# originalSWEEP.net
KiCad netlist of a schematic drawn in Altium Designer
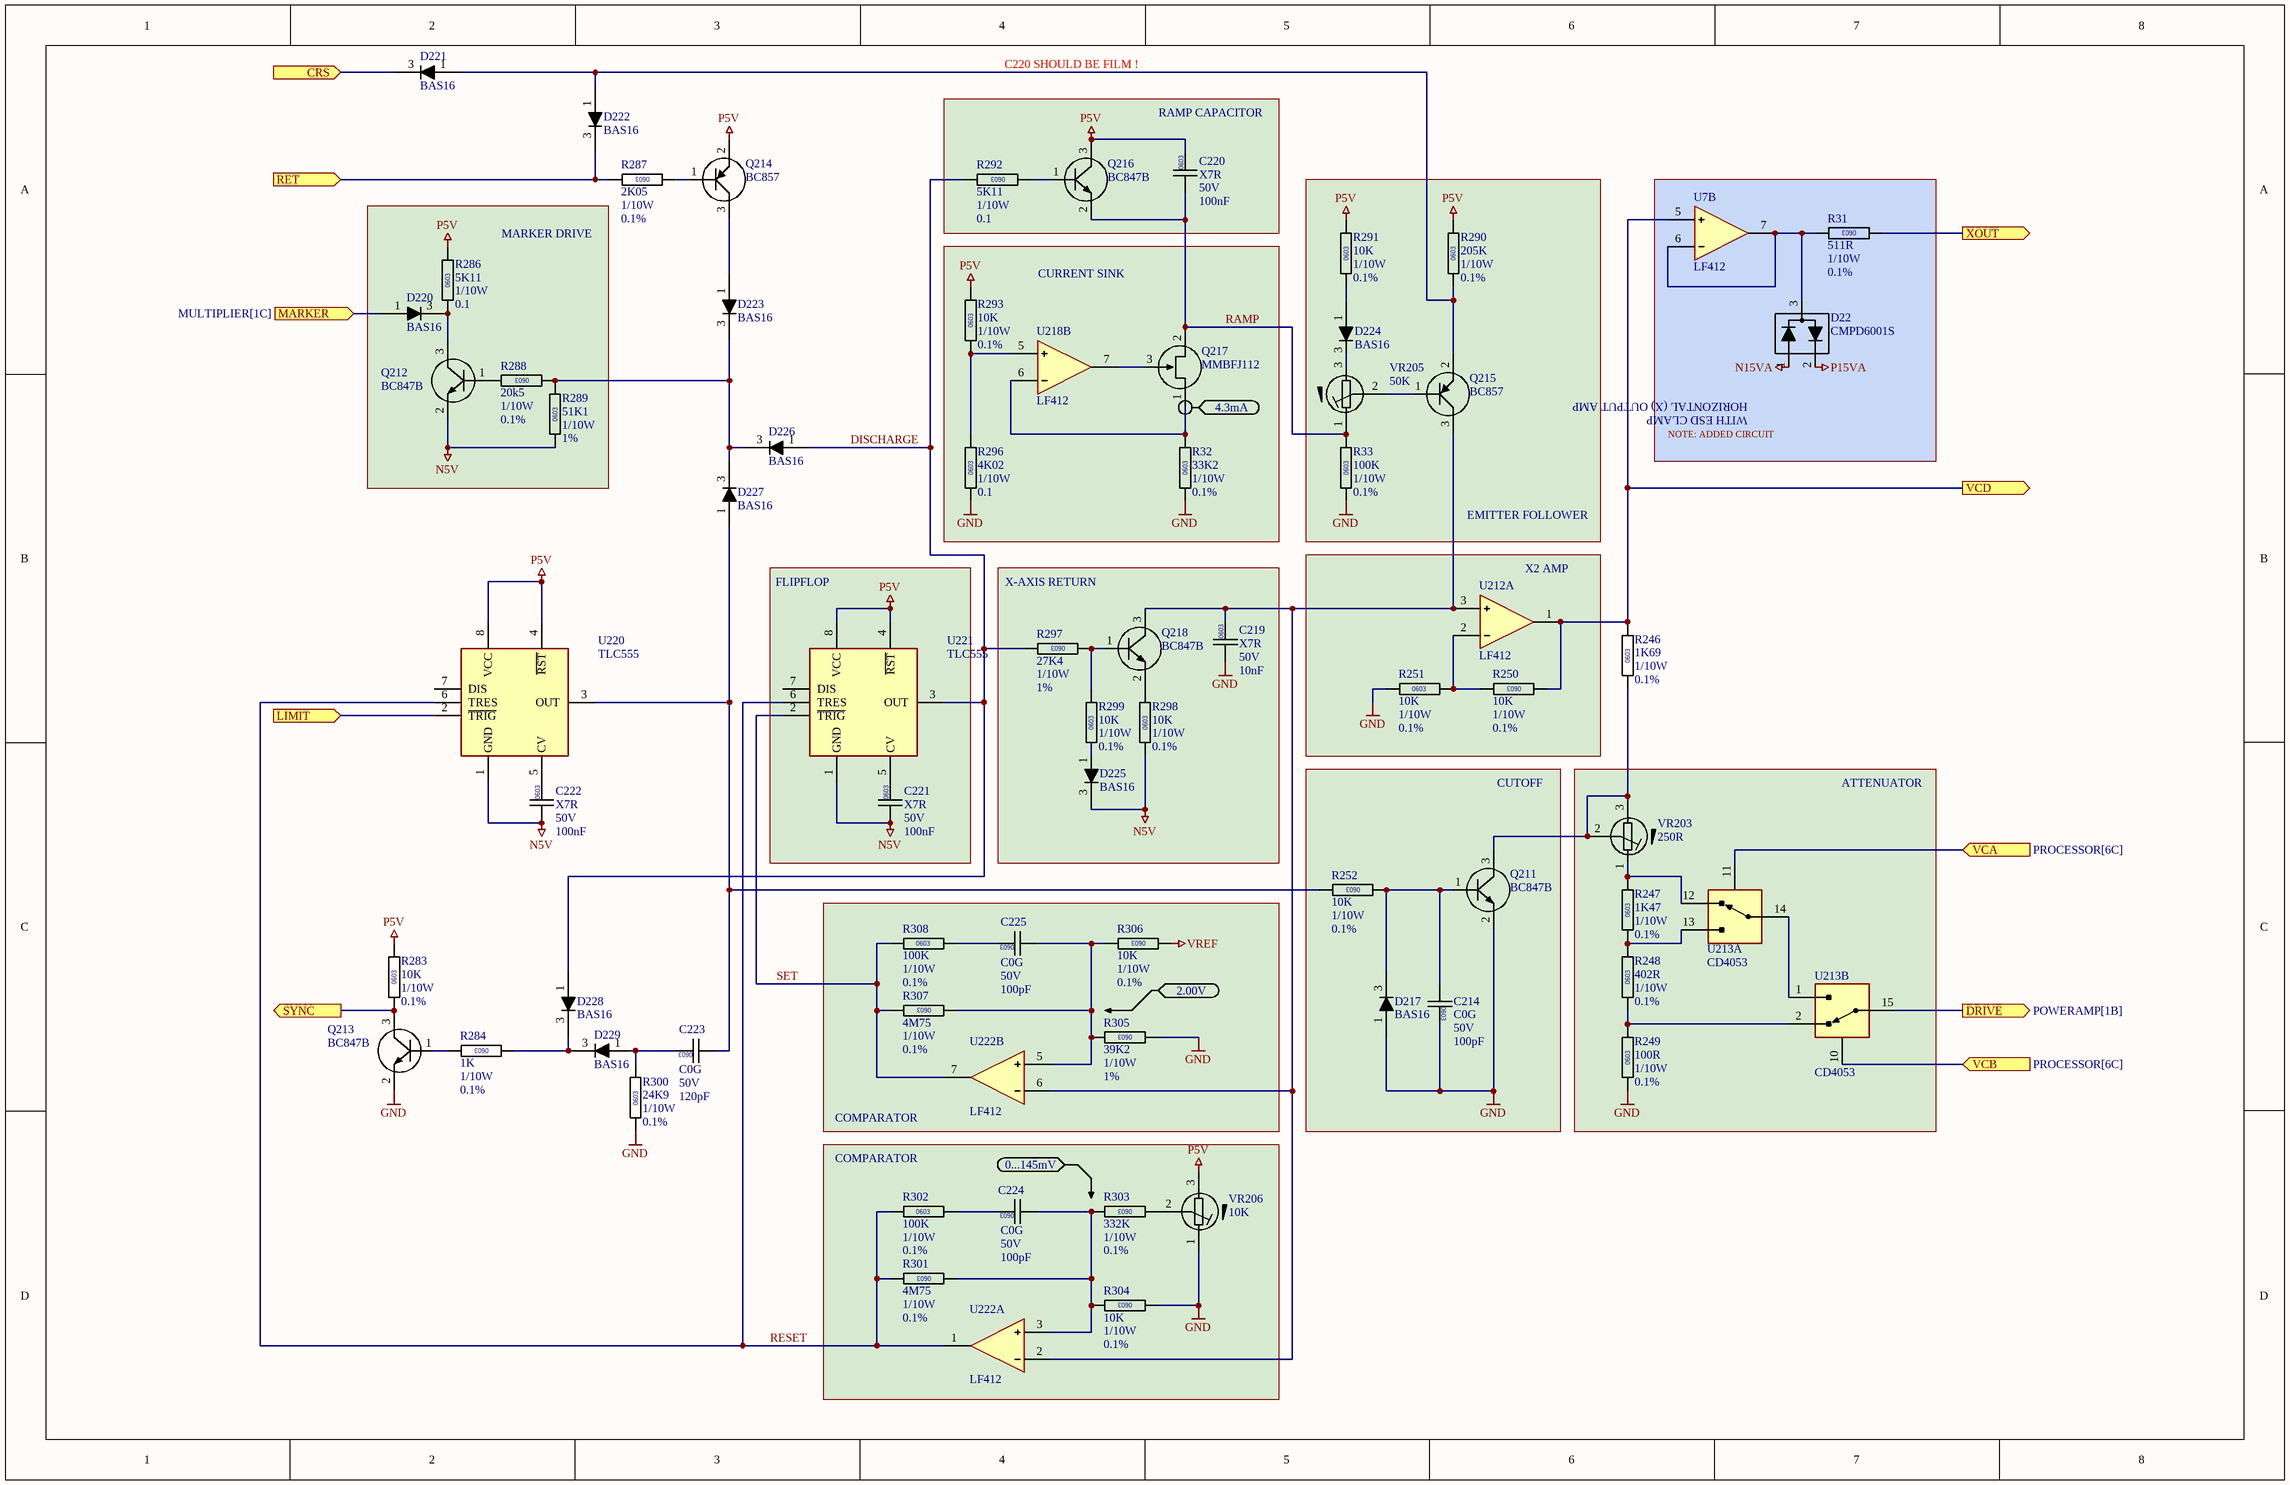
[diagram p0: originalSWEEP.SchDoc]

(export (version "E")
  (design (tool "Eeschema 10.0.6"))
  (components
    (comp (ref "C214")
      (value "CAP0603")
      (footprint "CAPC0603")
      (description "CAPACITOR,CERAMIC,100pF,50V,C0G,0603")
      (fields
        (field (name "DIELECTRIC") "C0G")
        (field (name "VOLTAGE") "50V")
        (field (name "CAPACITANCE") "100pF")
      )
      (libsource (lib "CAPACITORS") (part "CAPC-0603-100pF-50V-C0G"))
    )
    (comp (ref "C219")
      (value "CAP0603")
      (footprint "CAPC0603")
      (description "CAPACITOR,CERAMIC,10nF,50V,X7R,0603")
      (fields
        (field (name "DIELECTRIC") "X7R")
        (field (name "VOLTAGE") "50V")
        (field (name "CAPACITANCE") "10nF")
      )
      (libsource (lib "CAPACITORS") (part "CAPC-0603-10nF-50V-X7R"))
    )
    (comp (ref "C220")
      (value "CAP0603")
      (footprint "CAPC0603")
      (description "CAPACITOR,CERAMIC,100nF,50V,X7R,0603")
      (fields
        (field (name "DIELECTRIC") "X7R")
        (field (name "VOLTAGE") "50V")
        (field (name "CAPACITANCE") "100nF")
      )
      (libsource (lib "CAPACITORS") (part "CAPC-0603-100nF-50V-X7R"))
    )
    (comp (ref "C221")
      (value "CAP0603")
      (footprint "CAPC0603")
      (description "CAPACITOR,CERAMIC,100nF,50V,X7R,0603")
      (fields
        (field (name "DIELECTRIC") "X7R")
        (field (name "VOLTAGE") "50V")
        (field (name "CAPACITANCE") "100nF")
      )
      (libsource (lib "CAPACITORS") (part "CAPC-0603-100nF-50V-X7R"))
    )
    (comp (ref "C222")
      (value "CAP0603")
      (footprint "CAPC0603")
      (description "CAPACITOR,CERAMIC,100nF,50V,X7R,0603")
      (fields
        (field (name "DIELECTRIC") "X7R")
        (field (name "VOLTAGE") "50V")
        (field (name "CAPACITANCE") "100nF")
      )
      (libsource (lib "CAPACITORS") (part "CAPC-0603-100nF-50V-X7R"))
    )
    (comp (ref "C223")
      (value "CAP0603")
      (footprint "CAPC0603")
      (description "CAPACITOR,CERAMIC,120pF,50V,C0G,0603")
      (fields
        (field (name "DIELECTRIC") "C0G")
        (field (name "VOLTAGE") "50V")
        (field (name "CAPACITANCE") "120pF")
      )
      (libsource (lib "CAPACITORS") (part "CAPC-0603-120pF-50V-C0G"))
    )
    (comp (ref "C224")
      (value "CAP0603")
      (footprint "CAPC0603")
      (description "CAPACITOR,CERAMIC,100pF,50V,C0G,0603")
      (fields
        (field (name "DIELECTRIC") "C0G")
        (field (name "VOLTAGE") "50V")
        (field (name "CAPACITANCE") "100pF")
      )
      (libsource (lib "CAPACITORS") (part "CAPC-0603-100pF-50V-C0G"))
    )
    (comp (ref "C225")
      (value "CAP0603")
      (footprint "CAPC0603")
      (description "CAPACITOR,CERAMIC,100pF,50V,C0G,0603")
      (fields
        (field (name "DIELECTRIC") "C0G")
        (field (name "VOLTAGE") "50V")
        (field (name "CAPACITANCE") "100pF")
      )
      (libsource (lib "CAPACITORS") (part "CAPC-0603-100pF-50V-C0G"))
    )
    (comp (ref "D22")
      (value "CMPD6001S")
      (footprint "SOT23")
      (description "DIODE,75V,250mA,SOT23,500pA ULTRA LOW LEAKAGE")
      (libsource (lib "DIODES") (part "DIODE-CENTRALSEMI-CMPD6001S"))
    )
    (comp (ref "D217")
      (value "BAS16")
      (description "DIODE,RECTIFIER,75V,0.3A,BAS16,SOT23")
      (libsource (lib "DIODES") (part "DIODE-RECTIFIER-DIODES-BAS16-SOT23"))
    )
    (comp (ref "D220")
      (value "BAS16")
      (description "DIODE,RECTIFIER,75V,0.3A,BAS16,SOT23")
      (libsource (lib "DIODES") (part "DIODE-RECTIFIER-DIODES-BAS16-SOT23"))
    )
    (comp (ref "D221")
      (value "BAS16")
      (description "DIODE,RECTIFIER,75V,0.3A,BAS16,SOT23")
      (libsource (lib "DIODES") (part "DIODE-RECTIFIER-DIODES-BAS16-SOT23"))
    )
    (comp (ref "D222")
      (value "BAS16")
      (description "DIODE,RECTIFIER,75V,0.3A,BAS16,SOT23")
      (libsource (lib "DIODES") (part "DIODE-RECTIFIER-DIODES-BAS16-SOT23"))
    )
    (comp (ref "D223")
      (value "BAS16")
      (description "DIODE,RECTIFIER,75V,0.3A,BAS16,SOT23")
      (libsource (lib "DIODES") (part "DIODE-RECTIFIER-DIODES-BAS16-SOT23"))
    )
    (comp (ref "D224")
      (value "BAS16")
      (description "DIODE,RECTIFIER,75V,0.3A,BAS16,SOT23")
      (libsource (lib "DIODES") (part "DIODE-RECTIFIER-DIODES-BAS16-SOT23"))
    )
    (comp (ref "D225")
      (value "BAS16")
      (description "DIODE,RECTIFIER,75V,0.3A,BAS16,SOT23")
      (libsource (lib "DIODES") (part "DIODE-RECTIFIER-DIODES-BAS16-SOT23"))
    )
    (comp (ref "D226")
      (value "BAS16")
      (description "DIODE,RECTIFIER,75V,0.3A,BAS16,SOT23")
      (libsource (lib "DIODES") (part "DIODE-RECTIFIER-DIODES-BAS16-SOT23"))
    )
    (comp (ref "D227")
      (value "BAS16")
      (description "DIODE,RECTIFIER,75V,0.3A,BAS16,SOT23")
      (libsource (lib "DIODES") (part "DIODE-RECTIFIER-DIODES-BAS16-SOT23"))
    )
    (comp (ref "D228")
      (value "BAS16")
      (description "DIODE,RECTIFIER,75V,0.3A,BAS16,SOT23")
      (libsource (lib "DIODES") (part "DIODE-RECTIFIER-DIODES-BAS16-SOT23"))
    )
    (comp (ref "D229")
      (value "BAS16")
      (description "DIODE,RECTIFIER,75V,0.3A,BAS16,SOT23")
      (libsource (lib "DIODES") (part "DIODE-RECTIFIER-DIODES-BAS16-SOT23"))
    )
    (comp (ref "Q211")
      (value "BC847B")
      (footprint "SOT23")
      (description "XSTR,NPN,45V,0.1A,,BC847B,SOT23")
      (libsource (lib "TRANSISTORS") (part "XSTR-NPN-BC847"))
    )
    (comp (ref "Q212")
      (value "BC847B")
      (footprint "SOT23")
      (description "XSTR,NPN,45V,0.1A,,BC847B,SOT23")
      (libsource (lib "TRANSISTORS") (part "XSTR-NPN-BC847"))
    )
    (comp (ref "Q213")
      (value "BC847B")
      (footprint "SOT23")
      (description "XSTR,NPN,45V,0.1A,,BC847B,SOT23")
      (libsource (lib "TRANSISTORS") (part "XSTR-NPN-BC847"))
    )
    (comp (ref "Q214")
      (value "BC857")
      (footprint "SOT23")
      (description "XSTR,PNP,SOT23,BC857,SOT23")
      (libsource (lib "TRANSISTORS") (part "XSTR-PNP-BC857"))
    )
    (comp (ref "Q215")
      (value "BC857")
      (footprint "SOT23")
      (description "XSTR,PNP,SOT23,BC857,SOT23")
      (libsource (lib "TRANSISTORS") (part "XSTR-PNP-BC857"))
    )
    (comp (ref "Q216")
      (value "BC847B")
      (footprint "SOT23")
      (description "XSTR,NPN,45V,0.1A,,BC847B,SOT23")
      (libsource (lib "TRANSISTORS") (part "XSTR-NPN-BC847"))
    )
    (comp (ref "Q217")
      (value "MMBFJ112")
      (description "XSTR,JFET,NCHAN,ONSEMI,MMBFJ112,SOT23")
      (libsource (lib "TRANSISTORS") (part "XSTR-ONSEMI-J112-SOT23"))
    )
    (comp (ref "Q218")
      (value "BC847B")
      (footprint "SOT23")
      (description "XSTR,NPN,45V,0.1A,,BC847B,SOT23")
      (libsource (lib "TRANSISTORS") (part "XSTR-NPN-BC847"))
    )
    (comp (ref "R31")
      (value "511R")
      (footprint "RESC0603")
      (description "RESISTOR,511R,0.1%,100mW,0603 (1608)")
      (fields
        (field (name "POWER") "1/10W")
        (field (name "TOLERANCE") "0.1%")
        (field (name "Comment") "RESC0603")
      )
      (libsource (lib "RESISTORS") (part "RESC-0603-511R-0.1%"))
    )
    (comp (ref "R32")
      (value "33K2")
      (footprint "RESC0603")
      (description "RESISTOR,33K2,0.1%,100mW,0603 (1608)")
      (fields
        (field (name "POWER") "1/10W")
        (field (name "TOLERANCE") "0.1%")
        (field (name "Comment") "RESC0603")
      )
      (libsource (lib "RESISTORS") (part "RESC-0603-33K2-0.1%-1/10W"))
    )
    (comp (ref "R33")
      (value "100K")
      (footprint "RESC0603")
      (description "RESISTOR,100K,0.1%,100mW,0603 (1608)")
      (fields
        (field (name "POWER") "1/10W")
        (field (name "TOLERANCE") "0.1%")
        (field (name "Comment") "RESC0603")
      )
      (libsource (lib "RESISTORS") (part "RESC-0603-100K-0.1%-1/10W"))
    )
    (comp (ref "R246")
      (value "1K69")
      (footprint "RESC0603")
      (description "RESISTOR,1K69,0.1%,100mW,0603 (1608)")
      (fields
        (field (name "POWER") "1/10W")
        (field (name "TOLERANCE") "0.1%")
        (field (name "Comment") "RESC0603")
      )
      (libsource (lib "RESISTORS") (part "RESC-0603-1K69-0.1%-1/10W"))
    )
    (comp (ref "R247")
      (value "1K47")
      (footprint "RESC0603")
      (description "RESISTOR,1K47,0.1%,100mW,0603 (1608)")
      (fields
        (field (name "POWER") "1/10W")
        (field (name "TOLERANCE") "0.1%")
        (field (name "Comment") "RESC0603")
      )
      (libsource (lib "RESISTORS") (part "RESC-0603-1K47-0.1%-1/10W"))
    )
    (comp (ref "R248")
      (value "402R")
      (footprint "RESC0603")
      (description "RESISTOR,402R,0.1%,100mW,0603 (1608)")
      (fields
        (field (name "POWER") "1/10W")
        (field (name "TOLERANCE") "0.1%")
        (field (name "Comment") "RESC0603")
      )
      (libsource (lib "RESISTORS") (part "RESC-0603-402R-0.1%-1/10W"))
    )
    (comp (ref "R249")
      (value "100R")
      (footprint "RESC0603")
      (description "RESISTOR,100R,0.1%,100mW,0603 (1608)")
      (fields
        (field (name "POWER") "1/10W")
        (field (name "TOLERANCE") "0.1%")
        (field (name "Comment") "RESC0603")
      )
      (libsource (lib "RESISTORS") (part "RESC-0603-100R,0.1%-1/10W"))
    )
    (comp (ref "R250")
      (value "10K")
      (footprint "RESC0603")
      (description "RESISTOR,10K,0.1%,100mW,0603 (1608)")
      (fields
        (field (name "POWER") "1/10W")
        (field (name "TOLERANCE") "0.1%")
        (field (name "Comment") "RESC0603")
      )
      (libsource (lib "RESISTORS") (part "RESC-0603-10K-0.1%-1/10W"))
    )
    (comp (ref "R251")
      (value "10K")
      (footprint "RESC0603")
      (description "RESISTOR,10K,0.1%,100mW,0603 (1608)")
      (fields
        (field (name "POWER") "1/10W")
        (field (name "TOLERANCE") "0.1%")
        (field (name "Comment") "RESC0603")
      )
      (libsource (lib "RESISTORS") (part "RESC-0603-10K-0.1%-1/10W"))
    )
    (comp (ref "R252")
      (value "10K")
      (footprint "RESC0603")
      (description "RESISTOR,10K,0.1%,100mW,0603 (1608)")
      (fields
        (field (name "POWER") "1/10W")
        (field (name "TOLERANCE") "0.1%")
        (field (name "Comment") "RESC0603")
      )
      (libsource (lib "RESISTORS") (part "RESC-0603-10K-0.1%-1/10W"))
    )
    (comp (ref "R283")
      (value "10K")
      (footprint "RESC0603")
      (description "RESISTOR,10K,0.1%,100mW,0603 (1608)")
      (fields
        (field (name "POWER") "1/10W")
        (field (name "TOLERANCE") "0.1%")
        (field (name "Comment") "RESC0603")
      )
      (libsource (lib "RESISTORS") (part "RESC-0603-10K-0.1%-1/10W"))
    )
    (comp (ref "R284")
      (value "1K")
      (footprint "RESC0603")
      (description "RESISTOR,1K,0.1%,100mW,0603 (1608)")
      (fields
        (field (name "POWER") "1/10W")
        (field (name "TOLERANCE") "0.1%")
        (field (name "Comment") "RESC0603")
      )
      (libsource (lib "RESISTORS") (part "RESC-0603-1K-0.1%-1/10W"))
    )
    (comp (ref "R286")
      (value "5K11")
      (footprint "RESC0603")
      (description "RESISTOR,5K11,0.1%,100mW,0603 (1608)")
      (fields
        (field (name "POWER") "1/10W")
        (field (name "TOLERANCE") "0.1")
        (field (name "Comment") "RESC0603")
      )
      (libsource (lib "RESISTORS") (part "RESC-0603-5K11-0.1%-1/10W"))
    )
    (comp (ref "R287")
      (value "2K05")
      (footprint "RESC0603")
      (description "RESISTOR,2K05,0.11%,100mW,0603 (1608)")
      (fields
        (field (name "POWER") "1/10W")
        (field (name "TOLERANCE") "0.1%")
        (field (name "Comment") "RESC0603")
      )
      (libsource (lib "RESISTORS") (part "RESC-0603-2K05-0.1%-1/10W"))
    )
    (comp (ref "R288")
      (value "20k5")
      (footprint "RESC0603")
      (description "RESISTOR,20K5,0.1%,100mW,0603 (1608)")
      (fields
        (field (name "POWER") "1/10W")
        (field (name "TOLERANCE") "0.1%")
        (field (name "Comment") "RESC0603")
      )
      (libsource (lib "RESISTORS") (part "RESC-0603-20K5-0.1%-1/10W"))
    )
    (comp (ref "R289")
      (value "51K1")
      (footprint "RESC0603")
      (description "RESISTOR,51K1,1%,100mW,0603 (1608)")
      (fields
        (field (name "POWER") "1/10W")
        (field (name "TOLERANCE") "1%")
        (field (name "Comment") "RESC0603")
      )
      (libsource (lib "RESISTORS") (part "RESC-0603-51K1-1%-1/10W"))
    )
    (comp (ref "R290")
      (value "205K")
      (footprint "RESC0603")
      (description "RESISTOR,205K,0.1%,100mW,0603 (1608)")
      (fields
        (field (name "POWER") "1/10W")
        (field (name "TOLERANCE") "0.1%")
        (field (name "Comment") "RESC0603")
      )
      (libsource (lib "RESISTORS") (part "RESC-0603-205K-0.1%-1/10W"))
    )
    (comp (ref "R291")
      (value "10K")
      (footprint "RESC0603")
      (description "RESISTOR,10K,0.1%,100mW,0603 (1608)")
      (fields
        (field (name "POWER") "1/10W")
        (field (name "TOLERANCE") "0.1%")
        (field (name "Comment") "RESC0603")
      )
      (libsource (lib "RESISTORS") (part "RESC-0603-10K-0.1%-1/10W"))
    )
    (comp (ref "R292")
      (value "5K11")
      (footprint "RESC0603")
      (description "RESISTOR,5K11,0.1%,100mW,0603 (1608)")
      (fields
        (field (name "POWER") "1/10W")
        (field (name "TOLERANCE") "0.1")
        (field (name "Comment") "RESC0603")
      )
      (libsource (lib "RESISTORS") (part "RESC-0603-5K11-0.1%-1/10W"))
    )
    (comp (ref "R293")
      (value "10K")
      (footprint "RESC0603")
      (description "RESISTOR,10K,0.1%,100mW,0603 (1608)")
      (fields
        (field (name "POWER") "1/10W")
        (field (name "TOLERANCE") "0.1%")
        (field (name "Comment") "RESC0603")
      )
      (libsource (lib "RESISTORS") (part "RESC-0603-10K-0.1%-1/10W"))
    )
    (comp (ref "R296")
      (value "4K02")
      (footprint "RESC0603")
      (description "RESISTOR,4K02,0.1%,100mW,0603 (1608)")
      (fields
        (field (name "POWER") "1/10W")
        (field (name "TOLERANCE") "0.1")
        (field (name "Comment") "RESC0603")
      )
      (libsource (lib "RESISTORS") (part "RESC-0603-4K02-0.1%-1/10W"))
    )
    (comp (ref "R297")
      (value "27K4")
      (footprint "RESC0603")
      (description "RESISTOR,27K4,1%,100mW,0603 (1608)")
      (fields
        (field (name "POWER") "1/10W")
        (field (name "TOLERANCE") "1%")
        (field (name "Comment") "RESC0603")
      )
      (libsource (lib "RESISTORS") (part "RESC-0603-27K4-1%-1/10W"))
    )
    (comp (ref "R298")
      (value "10K")
      (footprint "RESC0603")
      (description "RESISTOR,10K,0.1%,100mW,0603 (1608)")
      (fields
        (field (name "POWER") "1/10W")
        (field (name "TOLERANCE") "0.1%")
        (field (name "Comment") "RESC0603")
      )
      (libsource (lib "RESISTORS") (part "RESC-0603-10K-0.1%-1/10W"))
    )
    (comp (ref "R299")
      (value "10K")
      (footprint "RESC0603")
      (description "RESISTOR,10K,0.1%,100mW,0603 (1608)")
      (fields
        (field (name "POWER") "1/10W")
        (field (name "TOLERANCE") "0.1%")
        (field (name "Comment") "RESC0603")
      )
      (libsource (lib "RESISTORS") (part "RESC-0603-10K-0.1%-1/10W"))
    )
    (comp (ref "R300")
      (value "24K9")
      (footprint "RESC0603")
      (description "RESISTOR,24K9,0.1%,100mW,0603 (1608)")
      (fields
        (field (name "POWER") "1/10W")
        (field (name "TOLERANCE") "0.1%")
        (field (name "Comment") "RESC0603")
      )
      (libsource (lib "RESISTORS") (part "RESC-0603-24K9-0.1%-1/10W"))
    )
    (comp (ref "R301")
      (value "4M75")
      (footprint "RESC0603")
      (description "RESISTOR,4M75,0.1%,100mW,0603 (1608)")
      (fields
        (field (name "POWER") "1/10W")
        (field (name "TOLERANCE") "0.1%")
        (field (name "Comment") "RESC0603")
      )
      (libsource (lib "RESISTORS") (part "RESC-0603-4M75-1%-1/10W"))
    )
    (comp (ref "R302")
      (value "100K")
      (footprint "RESC0603")
      (description "RESISTOR,100K,0.1%,100mW,0603 (1608)")
      (fields
        (field (name "POWER") "1/10W")
        (field (name "TOLERANCE") "0.1%")
        (field (name "Comment") "RESC0603")
      )
      (libsource (lib "RESISTORS") (part "RESC-0603-100K-0.1%-1/10W"))
    )
    (comp (ref "R303")
      (value "332K")
      (footprint "RESC0603")
      (description "RESISTOR,332K,0.1%,100mW,0603 (1608)")
      (fields
        (field (name "POWER") "1/10W")
        (field (name "TOLERANCE") "0.1%")
        (field (name "Comment") "RESC0603")
      )
      (libsource (lib "RESISTORS") (part "RESC-0603-332K-0.1%-1/10W"))
    )
    (comp (ref "R304")
      (value "10K")
      (footprint "RESC0603")
      (description "RESISTOR,10K,0.1%,100mW,0603 (1608)")
      (fields
        (field (name "POWER") "1/10W")
        (field (name "TOLERANCE") "0.1%")
        (field (name "Comment") "RESC0603")
      )
      (libsource (lib "RESISTORS") (part "RESC-0603-10K-0.1%-1/10W"))
    )
    (comp (ref "R305")
      (value "39K2")
      (footprint "RESC0603")
      (description "RESISTOR,39K2,0.1%,100mW,0603 (1608)")
      (fields
        (field (name "POWER") "1/10W")
        (field (name "TOLERANCE") "1%")
        (field (name "Comment") "RESC0603")
      )
      (libsource (lib "RESISTORS") (part "RESC-0603-39K2-0.1%-1/10W"))
    )
    (comp (ref "R306")
      (value "10K")
      (footprint "RESC0603")
      (description "RESISTOR,10K,0.1%,100mW,0603 (1608)")
      (fields
        (field (name "POWER") "1/10W")
        (field (name "TOLERANCE") "0.1%")
        (field (name "Comment") "RESC0603")
      )
      (libsource (lib "RESISTORS") (part "RESC-0603-10K-0.1%-1/10W"))
    )
    (comp (ref "R307")
      (value "4M75")
      (footprint "RESC0603")
      (description "RESISTOR,4M75,0.1%,100mW,0603 (1608)")
      (fields
        (field (name "POWER") "1/10W")
        (field (name "TOLERANCE") "0.1%")
        (field (name "Comment") "RESC0603")
      )
      (libsource (lib "RESISTORS") (part "RESC-0603-4M75-1%-1/10W"))
    )
    (comp (ref "R308")
      (value "100K")
      (footprint "RESC0603")
      (description "RESISTOR,100K,0.1%,100mW,0603 (1608)")
      (fields
        (field (name "POWER") "1/10W")
        (field (name "TOLERANCE") "0.1%")
        (field (name "Comment") "RESC0603")
      )
      (libsource (lib "RESISTORS") (part "RESC-0603-100K-0.1%-1/10W"))
    )
    (comp (ref "U7")
      (value "LF412")
      (footprint "SO127P600-8N")
      (description "IC,OPAMP JFET,DUAL,LF412,SO8")
      (libsource (lib "") (part "IC-TI-LF412-S08_1"))
    )
    (comp (ref "U212")
      (value "LF412")
      (footprint "SO127P600-8N")
      (description "IC,OPAMP JFET,DUAL,LF412,SO8")
      (libsource (lib "") (part "IC-TI-LF412-S08_1"))
    )
    (comp (ref "U213")
      (value "CD4053")
      (footprint "SO127P600-16N")
      (description "IC,MUX,TRIPLE 2:1 MUX,SPLIT BLOCKS")
      (libsource (lib "IC-4XXX") (part "IC-TI-CD4053-SPLIT"))
    )
    (comp (ref "U218")
      (value "LF412")
      (footprint "SO127P600-8N")
      (description "IC,OPAMP JFET,DUAL,LF412,SO8")
      (libsource (lib "") (part "IC-TI-LF412-S08_1"))
    )
    (comp (ref "U220")
      (value "TLC555")
      (footprint "SO127P600-8N")
      (description "IC,TIMER,CMOSE,TI,TLC555,SO8")
      (libsource (lib "IC-TIMING") (part "IC-TI-TLC555-SO8"))
    )
    (comp (ref "U221")
      (value "TLC555")
      (footprint "SO127P600-8N")
      (description "IC,TIMER,CMOSE,TI,TLC555,SO8")
      (libsource (lib "IC-TIMING") (part "IC-TI-TLC555-SO8"))
    )
    (comp (ref "U222")
      (value "LF412")
      (footprint "SO127P600-8N")
      (description "IC,OPAMP JFET,DUAL,LF412,SO8")
      (libsource (lib "IC-OPAMP") (part "IC-TI-LF412-S08"))
    )
    (comp (ref "VR203")
      (value "250R")
      (footprint "TRIMMER-BOURNS-3214X")
      (description "RESISTOR,MULTITURN,VERTICAL,5T,250R")
      (fields (field (name "Comment") "TRIMMER-BOURNS-3214X-1-251"))
      (libsource (lib "RESISTORS") (part "TRIMMER-BOURNS-3214X-1-251"))
    )
    (comp (ref "VR205")
      (value "50K")
      (footprint "TRIMMER-BOURNS-3214X")
      (description "RESISTOR,MULTITURN,VERTICAL,5T,50K")
      (fields (field (name "Comment") "TRIMMER-BOURNS-3214X-1-503"))
      (libsource (lib "RESISTORS") (part "TRIMMER-BOURNS-3214X-1-503"))
    )
    (comp (ref "VR206")
      (value "10K")
      (footprint "TRIMMER-BOURNS-3214X")
      (description "RESISTOR,MULTITURN,VERTICAL,5T,10K")
      (fields (field (name "Comment") "TRIMMER-BOURNS-3214X-1-103E"))
      (libsource (lib "RESISTORS") (part "TRIMMER-BOURNS-3214X-1-103E"))
    )
  )
  (nets
    (net (code "1") (name "/CRS") (class "Default")
      (node (ref "D221") (pin "3") (pinfunction "K_3") (pintype "passive"))
    )
    (net (code "2") (name "/DISCHARGE") (class "Default")
      (node (ref "D226") (pin "1") (pinfunction "A_1") (pintype "passive"))
      (node (ref "D228") (pin "1") (pinfunction "A_1") (pintype "passive"))
      (node (ref "R292") (pin "2") (pintype "passive"))
      (node (ref "R297") (pin "1") (pintype "passive"))
      (node (ref "U221") (pin "3") (pinfunction "OUT_3") (pintype "passive"))
    )
    (net (code "3") (name "/DRIVE") (class "Default")
      (node (ref "U213") (pin "15") (pinfunction "X2_15") (pintype "passive"))
    )
    (net (code "4") (name "/LIMIT") (class "Default")
      (node (ref "U220") (pin "2") (pinfunction "~{TRIG}_2") (pintype "passive"))
    )
    (net (code "5") (name "/MARKER") (class "Default")
      (node (ref "D220") (pin "1") (pinfunction "A_1") (pintype "passive"))
    )
    (net (code "6") (name "/RAMP") (class "Default")
      (node (ref "C220") (pin "2") (pintype "passive"))
      (node (ref "Q216") (pin "2") (pinfunction "E_2") (pintype "passive"))
      (node (ref "Q217") (pin "2") (pinfunction "S_2") (pintype "passive"))
      (node (ref "R33") (pin "1") (pintype "passive"))
      (node (ref "VR205") (pin "1") (pinfunction "1_1") (pintype "passive"))
    )
    (net (code "7") (name "/RESET") (class "Default")
      (node (ref "R301") (pin "1") (pintype "passive"))
      (node (ref "R302") (pin "1") (pintype "passive"))
      (node (ref "U220") (pin "6") (pinfunction "TRES_6") (pintype "passive"))
      (node (ref "U221") (pin "6") (pinfunction "TRES_6") (pintype "passive"))
      (node (ref "U222") (pin "1") (pinfunction "O_1") (pintype "passive"))
    )
    (net (code "8") (name "/RET") (class "Default")
      (node (ref "D222") (pin "3") (pinfunction "K_3") (pintype "passive"))
      (node (ref "R287") (pin "1") (pintype "passive"))
    )
    (net (code "9") (name "/SET") (class "Default")
      (node (ref "R307") (pin "1") (pintype "passive"))
      (node (ref "R308") (pin "1") (pintype "passive"))
      (node (ref "U221") (pin "2") (pinfunction "~{TRIG}_2") (pintype "passive"))
      (node (ref "U222") (pin "7") (pinfunction "O_7") (pintype "passive"))
    )
    (net (code "10") (name "/SYNC") (class "Default")
      (node (ref "Q213") (pin "3") (pinfunction "C_3") (pintype "passive"))
      (node (ref "R283") (pin "2") (pintype "passive"))
    )
    (net (code "11") (name "/VCA") (class "Default")
      (node (ref "U213") (pin "11") (pinfunction "X3_11") (pintype "passive"))
    )
    (net (code "12") (name "/VCB") (class "Default")
      (node (ref "U213") (pin "10") (pinfunction "A_10") (pintype "passive"))
    )
    (net (code "13") (name "/VCD") (class "Default")
      (node (ref "R246") (pin "1") (pintype "passive"))
      (node (ref "R250") (pin "2") (pintype "passive"))
      (node (ref "U212") (pin "1") (pinfunction "O_1") (pintype "passive"))
      (node (ref "U7") (pin "5") (pinfunction "+_5") (pintype "passive"))
    )
    (net (code "14") (name "/XOUT") (class "Default") (node (ref "R31") (pin "2") (pintype "passive")))
    (net (code "15") (name "GND") (class "Default")
      (node (ref "C214") (pin "1") (pintype "passive"))
      (node (ref "C219") (pin "2") (pintype "passive"))
      (node (ref "D217") (pin "1") (pinfunction "A_1") (pintype "passive"))
      (node (ref "Q211") (pin "2") (pinfunction "E_2") (pintype "passive"))
      (node (ref "Q213") (pin "2") (pinfunction "E_2") (pintype "passive"))
      (node (ref "R249") (pin "2") (pintype "passive"))
      (node (ref "R251") (pin "2") (pintype "passive"))
      (node (ref "R296") (pin "2") (pintype "passive"))
      (node (ref "R300") (pin "2") (pintype "passive"))
      (node (ref "R304") (pin "2") (pintype "passive"))
      (node (ref "R305") (pin "2") (pintype "passive"))
      (node (ref "R32") (pin "2") (pintype "passive"))
      (node (ref "R33") (pin "2") (pintype "passive"))
      (node (ref "VR206") (pin "1") (pinfunction "1_1") (pintype "passive"))
    )
    (net (code "16") (name "N5V") (class "Default")
      (node (ref "C221") (pin "2") (pintype "passive"))
      (node (ref "C222") (pin "2") (pintype "passive"))
      (node (ref "D225") (pin "3") (pinfunction "K_3") (pintype "passive"))
      (node (ref "Q212") (pin "2") (pinfunction "E_2") (pintype "passive"))
      (node (ref "R289") (pin "2") (pintype "passive"))
      (node (ref "R298") (pin "2") (pintype "passive"))
      (node (ref "U220") (pin "1") (pinfunction "GND_1") (pintype "passive"))
      (node (ref "U221") (pin "1") (pinfunction "GND_1") (pintype "passive"))
    )
    (net (code "17") (name "N15VA") (class "Default")
      (node (ref "D22") (pin "1") (pinfunction "K_1") (pintype "passive"))
    )
    (net (code "18") (name "Net-(C224-Pad1)") (class "Default")
      (node (ref "C224") (pin "1") (pintype "passive"))
      (node (ref "R302") (pin "2") (pintype "passive"))
    )
    (net (code "19") (name "Net-(C225-Pad1)") (class "Default")
      (node (ref "C225") (pin "1") (pintype "passive"))
      (node (ref "R308") (pin "2") (pintype "passive"))
    )
    (net (code "20") (name "Net-(D217-K)") (class "Default")
      (node (ref "C214") (pin "2") (pintype "passive"))
      (node (ref "D217") (pin "3") (pinfunction "K_3") (pintype "passive"))
      (node (ref "Q211") (pin "1") (pinfunction "B_1") (pintype "passive"))
      (node (ref "R252") (pin "2") (pintype "passive"))
    )
    (net (code "21") (name "Net-(D220-K)") (class "Default")
      (node (ref "D220") (pin "3") (pinfunction "K_3") (pintype "passive"))
      (node (ref "Q212") (pin "3") (pinfunction "C_3") (pintype "passive"))
      (node (ref "R286") (pin "2") (pintype "passive"))
    )
    (net (code "22") (name "Net-(D221-A)") (class "Default")
      (node (ref "D221") (pin "1") (pinfunction "A_1") (pintype "passive"))
      (node (ref "D222") (pin "1") (pinfunction "A_1") (pintype "passive"))
      (node (ref "Q215") (pin "2") (pinfunction "E_2") (pintype "passive"))
      (node (ref "R290") (pin "2") (pintype "passive"))
    )
    (net (code "23") (name "Net-(D223-A)") (class "Default")
      (node (ref "D223") (pin "1") (pinfunction "A_1") (pintype "passive"))
      (node (ref "Q214") (pin "3") (pinfunction "C_3") (pintype "passive"))
    )
    (net (code "24") (name "Net-(D223-K)") (class "Default")
      (node (ref "D223") (pin "3") (pinfunction "K_3") (pintype "passive"))
      (node (ref "D226") (pin "3") (pinfunction "K_3") (pintype "passive"))
      (node (ref "D227") (pin "3") (pinfunction "K_3") (pintype "passive"))
      (node (ref "R288") (pin "2") (pintype "passive"))
      (node (ref "R289") (pin "1") (pintype "passive"))
    )
    (net (code "25") (name "Net-(D224-A)") (class "Default")
      (node (ref "D224") (pin "1") (pinfunction "A_1") (pintype "passive"))
      (node (ref "R291") (pin "2") (pintype "passive"))
    )
    (net (code "26") (name "Net-(D224-K)") (class "Default")
      (node (ref "D224") (pin "3") (pinfunction "K_3") (pintype "passive"))
      (node (ref "VR205") (pin "3") (pinfunction "3_3") (pintype "passive"))
    )
    (net (code "27") (name "Net-(D225-A)") (class "Default")
      (node (ref "D225") (pin "1") (pinfunction "A_1") (pintype "passive"))
      (node (ref "R299") (pin "2") (pintype "passive"))
    )
    (net (code "28") (name "Net-(D227-A)") (class "Default")
      (node (ref "C223") (pin "2") (pintype "passive"))
      (node (ref "D227") (pin "1") (pinfunction "A_1") (pintype "passive"))
      (node (ref "R252") (pin "1") (pintype "passive"))
      (node (ref "U220") (pin "3") (pinfunction "OUT_3") (pintype "passive"))
    )
    (net (code "29") (name "Net-(D228-K)") (class "Default")
      (node (ref "D228") (pin "3") (pinfunction "K_3") (pintype "passive"))
      (node (ref "D229") (pin "3") (pinfunction "K_3") (pintype "passive"))
      (node (ref "R284") (pin "2") (pintype "passive"))
    )
    (net (code "30") (name "Net-(D229-A)") (class "Default")
      (node (ref "C223") (pin "1") (pintype "passive"))
      (node (ref "D229") (pin "1") (pinfunction "A_1") (pintype "passive"))
      (node (ref "R300") (pin "1") (pintype "passive"))
    )
    (net (code "31") (name "Net-(Q211-C)") (class "Default")
      (node (ref "Q211") (pin "3") (pinfunction "C_3") (pintype "passive"))
      (node (ref "R246") (pin "2") (pintype "passive"))
      (node (ref "VR203") (pin "2") (pinfunction "2_2") (pintype "passive"))
      (node (ref "VR203") (pin "3") (pinfunction "3_3") (pintype "passive"))
    )
    (net (code "32") (name "Net-(Q212-B)") (class "Default")
      (node (ref "Q212") (pin "1") (pinfunction "B_1") (pintype "passive"))
      (node (ref "R288") (pin "1") (pintype "passive"))
    )
    (net (code "33") (name "Net-(Q213-B)") (class "Default")
      (node (ref "Q213") (pin "1") (pinfunction "B_1") (pintype "passive"))
      (node (ref "R284") (pin "1") (pintype "passive"))
    )
    (net (code "34") (name "Net-(Q214-B)") (class "Default")
      (node (ref "Q214") (pin "1") (pinfunction "B_1") (pintype "passive"))
      (node (ref "R287") (pin "2") (pintype "passive"))
    )
    (net (code "35") (name "Net-(Q215-B)") (class "Default")
      (node (ref "Q215") (pin "1") (pinfunction "B_1") (pintype "passive"))
      (node (ref "VR205") (pin "2") (pinfunction "2_2") (pintype "passive"))
    )
    (net (code "36") (name "Net-(Q215-C)") (class "Default")
      (node (ref "C219") (pin "1") (pintype "passive"))
      (node (ref "Q215") (pin "3") (pinfunction "C_3") (pintype "passive"))
      (node (ref "Q218") (pin "3") (pinfunction "C_3") (pintype "passive"))
      (node (ref "U212") (pin "3") (pinfunction "+_3") (pintype "passive"))
      (node (ref "U222") (pin "2") (pinfunction "-_2") (pintype "passive"))
      (node (ref "U222") (pin "6") (pinfunction "-_6") (pintype "passive"))
    )
    (net (code "37") (name "Net-(Q216-B)") (class "Default")
      (node (ref "Q216") (pin "1") (pinfunction "B_1") (pintype "passive"))
      (node (ref "R292") (pin "1") (pintype "passive"))
    )
    (net (code "38") (name "Net-(Q217-D)") (class "Default")
      (node (ref "Q217") (pin "1") (pinfunction "D_1") (pintype "passive"))
      (node (ref "R32") (pin "1") (pintype "passive"))
      (node (ref "U218") (pin "6") (pinfunction "-_6") (pintype "passive"))
    )
    (net (code "39") (name "Net-(Q217-G)") (class "Default")
      (node (ref "Q217") (pin "3") (pinfunction "G_3") (pintype "passive"))
      (node (ref "U218") (pin "7") (pinfunction "O_7") (pintype "passive"))
    )
    (net (code "40") (name "Net-(Q218-B)") (class "Default")
      (node (ref "Q218") (pin "1") (pinfunction "B_1") (pintype "passive"))
      (node (ref "R297") (pin "2") (pintype "passive"))
      (node (ref "R299") (pin "1") (pintype "passive"))
    )
    (net (code "41") (name "Net-(Q218-E)") (class "Default")
      (node (ref "Q218") (pin "2") (pinfunction "E_2") (pintype "passive"))
      (node (ref "R298") (pin "1") (pintype "passive"))
    )
    (net (code "42") (name "Net-(R303-Pad2)") (class "Default")
      (node (ref "R303") (pin "2") (pintype "passive"))
      (node (ref "VR206") (pin "2") (pinfunction "2_2") (pintype "passive"))
    )
    (net (code "43") (name "Net-(U7B--)") (class "Default")
      (node (ref "D22") (pin "3") (pinfunction "A_3") (pintype "passive"))
      (node (ref "R31") (pin "1") (pintype "passive"))
      (node (ref "U7") (pin "6") (pinfunction "-_6") (pintype "passive"))
      (node (ref "U7") (pin "7") (pinfunction "O_7") (pintype "passive"))
    )
    (net (code "44") (name "Net-(U212A--)") (class "Default")
      (node (ref "R250") (pin "1") (pintype "passive"))
      (node (ref "R251") (pin "1") (pintype "passive"))
      (node (ref "U212") (pin "2") (pinfunction "-_2") (pintype "passive"))
    )
    (net (code "45") (name "Net-(U213A-X)") (class "Default")
      (node (ref "R247") (pin "2") (pintype "passive"))
      (node (ref "R248") (pin "1") (pintype "passive"))
      (node (ref "U213") (pin "13") (pinfunction "X_13") (pintype "passive"))
    )
    (net (code "46") (name "Net-(U213A-X0)") (class "Default")
      (node (ref "R247") (pin "1") (pintype "passive"))
      (node (ref "U213") (pin "12") (pinfunction "X0_12") (pintype "passive"))
      (node (ref "VR203") (pin "1") (pinfunction "1_1") (pintype "passive"))
    )
    (net (code "47") (name "Net-(U213A-X1)") (class "Default")
      (node (ref "U213") (pin "1") (pinfunction "Y0_1") (pintype "passive"))
      (node (ref "U213") (pin "14") (pinfunction "X1_14") (pintype "passive"))
    )
    (net (code "48") (name "Net-(U213B-Y2)") (class "Default")
      (node (ref "R248") (pin "2") (pintype "passive"))
      (node (ref "R249") (pin "1") (pintype "passive"))
      (node (ref "U213") (pin "2") (pinfunction "Y2_2") (pintype "passive"))
    )
    (net (code "49") (name "Net-(U218B-+)") (class "Default")
      (node (ref "R293") (pin "2") (pintype "passive"))
      (node (ref "R296") (pin "1") (pintype "passive"))
      (node (ref "U218") (pin "5") (pinfunction "+_5") (pintype "passive"))
    )
    (net (code "50") (name "Net-(U220-CV)") (class "Default")
      (node (ref "C222") (pin "1") (pintype "passive"))
      (node (ref "U220") (pin "5") (pinfunction "CV_5") (pintype "passive"))
    )
    (net (code "51") (name "Net-(U221-CV)") (class "Default")
      (node (ref "C221") (pin "1") (pintype "passive"))
      (node (ref "U221") (pin "5") (pinfunction "CV_5") (pintype "passive"))
    )
    (net (code "52") (name "Net-(U222A-+)") (class "Default")
      (node (ref "C224") (pin "2") (pintype "passive"))
      (node (ref "R301") (pin "2") (pintype "passive"))
      (node (ref "R303") (pin "1") (pintype "passive"))
      (node (ref "R304") (pin "1") (pintype "passive"))
      (node (ref "U222") (pin "3") (pinfunction "+_3") (pintype "passive"))
    )
    (net (code "53") (name "Net-(U222B-+)") (class "Default")
      (node (ref "C225") (pin "2") (pintype "passive"))
      (node (ref "R305") (pin "1") (pintype "passive"))
      (node (ref "R306") (pin "1") (pintype "passive"))
      (node (ref "R307") (pin "2") (pintype "passive"))
      (node (ref "U222") (pin "5") (pinfunction "+_5") (pintype "passive"))
    )
    (net (code "54") (name "P5V") (class "Default")
      (node (ref "C220") (pin "1") (pintype "passive"))
      (node (ref "Q214") (pin "2") (pinfunction "E_2") (pintype "passive"))
      (node (ref "Q216") (pin "3") (pinfunction "C_3") (pintype "passive"))
      (node (ref "R283") (pin "1") (pintype "passive"))
      (node (ref "R286") (pin "1") (pintype "passive"))
      (node (ref "R290") (pin "1") (pintype "passive"))
      (node (ref "R291") (pin "1") (pintype "passive"))
      (node (ref "R293") (pin "1") (pintype "passive"))
      (node (ref "U220") (pin "4") (pinfunction "~{RST}_4") (pintype "passive"))
      (node (ref "U220") (pin "8") (pinfunction "VCC_8") (pintype "passive"))
      (node (ref "U221") (pin "4") (pinfunction "~{RST}_4") (pintype "passive"))
      (node (ref "U221") (pin "8") (pinfunction "VCC_8") (pintype "passive"))
      (node (ref "VR206") (pin "3") (pinfunction "3_3") (pintype "passive"))
    )
    (net (code "55") (name "P15VA") (class "Default")
      (node (ref "D22") (pin "2") (pinfunction "A_2") (pintype "passive"))
    )
    (net (code "56") (name "VREF") (class "Default") (node (ref "R306") (pin "2") (pintype "passive")))
    (net (code "57") (name "unconnected-(U220-DIS-Pad7)") (class "Default")
      (node (ref "U220") (pin "7") (pinfunction "DIS_7") (pintype "passive"))
    )
    (net (code "58") (name "unconnected-(U221-DIS-Pad7)") (class "Default")
      (node (ref "U221") (pin "7") (pinfunction "DIS_7") (pintype "passive"))
    )
  )
)
